# ST_LINK_V2.net
KiCad netlist of a schematic drawn in Altium Designer
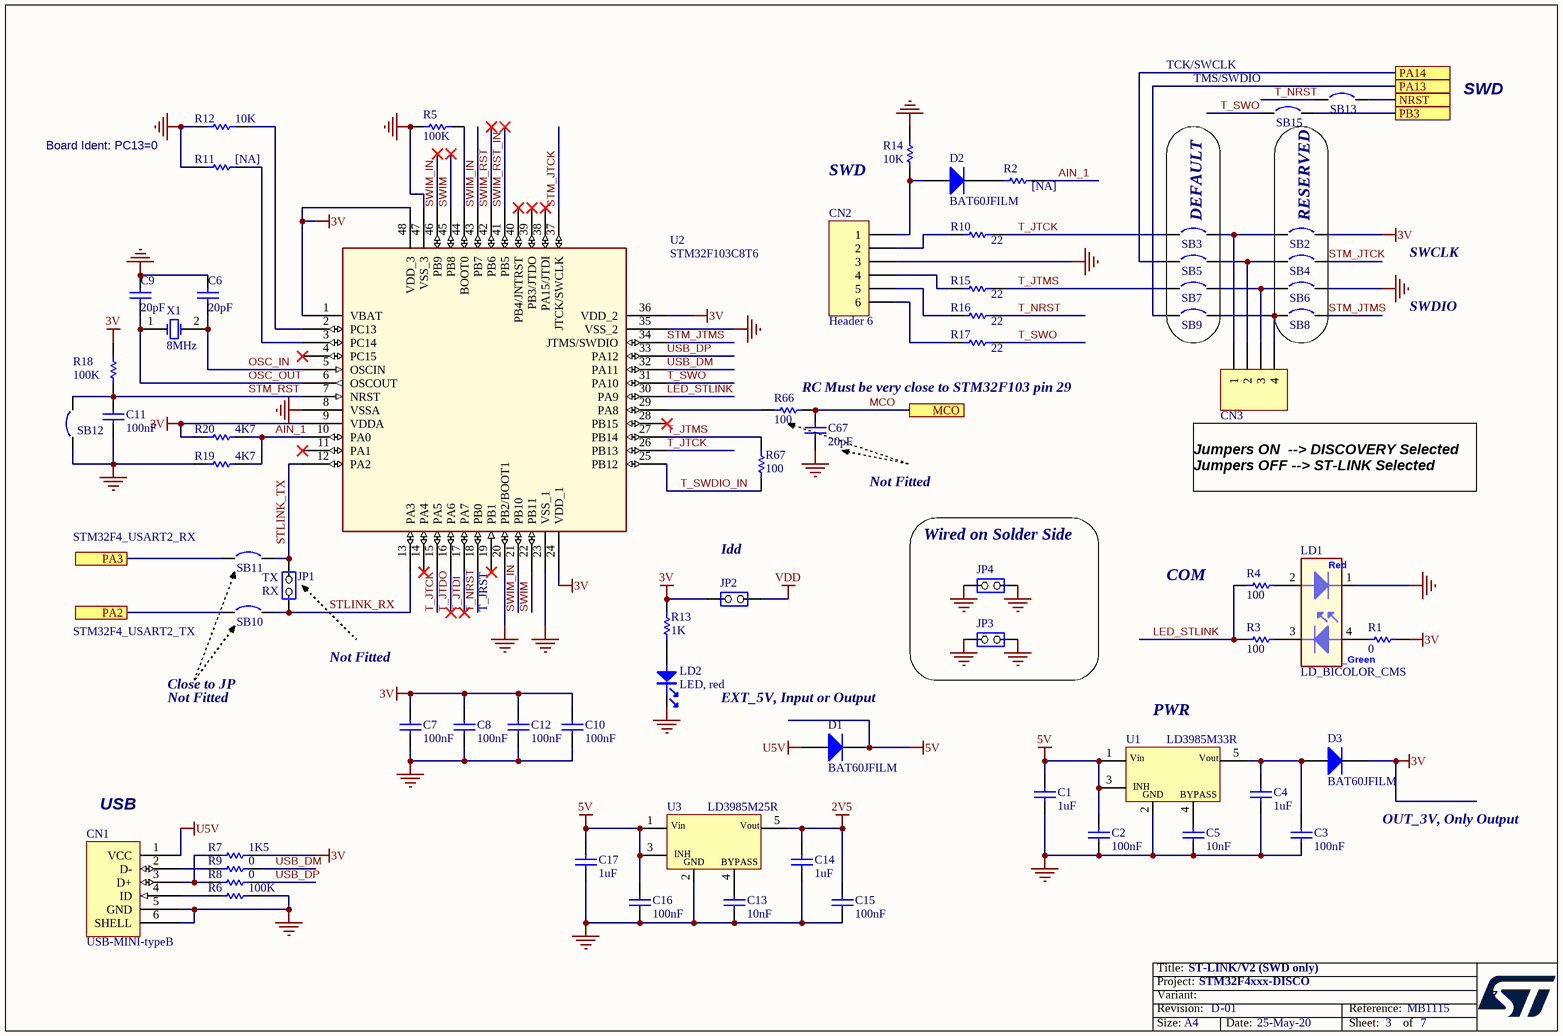
[diagram p0: ST_LINK_V2.SCHDOC]

(export (version "E")
  (design (tool "Eeschema 10.0.6"))
  (components
    (comp (ref "C1")
      (value "1uF")
      (footprint "0603C (Primary)")
      (description "Capacitor,1uF,16V,X5R,10%,0603,YAGEO")
      (libsource (lib "MCD_TOOLS") (part "Cap_1uF_X5R_10%_0603"))
    )
    (comp (ref "C2")
      (value "100nF")
      (footprint "0402C (Primary)")
      (description "Capacitor,100nF,16V,X7R,10%,0402,YAGEO")
      (libsource (lib "MCD_TOOLS") (part "Cap_100nF_X7R_10%_0402"))
    )
    (comp (ref "C3")
      (value "100nF")
      (footprint "0402C (Primary)")
      (description "Capacitor,100nF,16V,X7R,10%,0402,YAGEO")
      (libsource (lib "MCD_TOOLS") (part "Cap_100nF_X7R_10%_0402"))
    )
    (comp (ref "C4")
      (value "1uF")
      (footprint "0603C (Primary)")
      (description "Capacitor,1uF,16V,X5R,10%,0603,YAGEO")
      (libsource (lib "MCD_TOOLS") (part "Cap_1uF_X5R_10%_0603"))
    )
    (comp (ref "C5")
      (value "10nF")
      (footprint "0603C (Primary)")
      (description "Capacitor,10nF,50V,X7R,10%,0603,YAGEO")
      (libsource (lib "MCD_TOOLS") (part "Cap_10nF_X7R_10%_0603"))
    )
    (comp (ref "C6")
      (value "20pF")
      (footprint "0402C (Primary)")
      (description "Capacitor,20pF,50V,NPO,5%,0402,YAGEO")
      (libsource (lib "MCD_TOOLS") (part "Cap_20pF_NPO_5%_0402"))
    )
    (comp (ref "C7")
      (value "100nF")
      (footprint "0402C (Primary)")
      (description "Capacitor,100nF,16V,X7R,10%,0402,YAGEO")
      (libsource (lib "MCD_TOOLS") (part "Cap_100nF_X7R_10%_0402"))
    )
    (comp (ref "C8")
      (value "100nF")
      (footprint "0402C (Primary)")
      (description "Capacitor,100nF,16V,X7R,10%,0402,YAGEO")
      (libsource (lib "MCD_TOOLS") (part "Cap_100nF_X7R_10%_0402"))
    )
    (comp (ref "C9")
      (value "20pF")
      (footprint "0402C (Primary)")
      (description "Capacitor,20pF,50V,NPO,5%,0402,YAGEO")
      (libsource (lib "MCD_TOOLS") (part "Cap_20pF_NPO_5%_0402"))
    )
    (comp (ref "C10")
      (value "100nF")
      (footprint "0402C (Primary)")
      (description "Capacitor,100nF,16V,X7R,10%,0402,YAGEO")
      (libsource (lib "MCD_TOOLS") (part "Cap_100nF_X7R_10%_0402"))
    )
    (comp (ref "C11")
      (value "100nF")
      (footprint "0402C (Primary)")
      (description "Capacitor,100nF,16V,X7R,10%,0402,YAGEO")
      (libsource (lib "MCD_TOOLS") (part "Cap_100nF_X7R_10%_0402"))
    )
    (comp (ref "C12")
      (value "100nF")
      (footprint "0402C (Primary)")
      (description "Capacitor,100nF,16V,X7R,10%,0402,YAGEO")
      (libsource (lib "MCD_TOOLS") (part "Cap_100nF_X7R_10%_0402"))
    )
    (comp (ref "C13")
      (value "10nF")
      (footprint "0603C (Primary)")
      (description "Capacitor,10nF,50V,X7R,10%,0603,YAGEO")
      (libsource (lib "MCD_TOOLS") (part "Cap_10nF_X7R_10%_0603"))
    )
    (comp (ref "C14")
      (value "1uF")
      (footprint "0603C (Primary)")
      (description "Capacitor,1uF,16V,X5R,10%,0603,YAGEO")
      (libsource (lib "MCD_TOOLS") (part "Cap_1uF_X5R_10%_0603"))
    )
    (comp (ref "C15")
      (value "100nF")
      (footprint "0402C (Primary)")
      (description "Capacitor,100nF,16V,X7R,10%,0402,YAGEO")
      (libsource (lib "MCD_TOOLS") (part "Cap_100nF_X7R_10%_0402"))
    )
    (comp (ref "C16")
      (value "100nF")
      (footprint "0402C (Primary)")
      (description "Capacitor,100nF,16V,X7R,10%,0402,YAGEO")
      (libsource (lib "MCD_TOOLS") (part "Cap_100nF_X7R_10%_0402"))
    )
    (comp (ref "C17")
      (value "1uF")
      (footprint "0603C (Primary)")
      (description "Capacitor,1uF,16V,X5R,10%,0603,YAGEO")
      (libsource (lib "MCD_TOOLS") (part "Cap_1uF_X5R_10%_0603"))
    )
    (comp (ref "C67")
      (value "20pF")
      (footprint "0402C (Primary)")
      (description "Capacitor,20pF,50V,NPO,5%,0402,YAGEO")
      (libsource (lib "MCD_TOOLS") (part "Cap_20pF_NPO_5%_0402"))
    )
    (comp (ref "CN1")
      (value "USB-MINI-typeB")
      (footprint "USB-MINI-B-SMD (Primary)")
      (description "USB-MINI-typeB connector")
      (libsource (lib "MCD_TOOLS") (part "USB-MINI-typeB connector"))
    )
    (comp (ref "CN2")
      (value "Header 6")
      (footprint "HDR1X6 (Primary)")
      (description "Header, 6-Pin")
      (fields (field (name "PUBLISHER") "Altium Limited"))
      (libsource (lib "Miscellaneous Connectors") (part "Header 6"))
    )
    (comp (ref "CN3")
      (value "Header 4")
      (footprint "Header 4 (Primary)")
      (description "Header, 4-Pin")
      (fields (field (name "PUBLISHER") "Altium Limited"))
      (libsource (lib "MB963_1") (part "Header 4"))
    )
    (comp (ref "D1")
      (value "BAT60JFILM")
      (footprint "SOD323/A (Primary)")
      (libsource (lib "MCD_TOOLS") (part "BAT60JFILM"))
    )
    (comp (ref "D2")
      (value "BAT60JFILM")
      (footprint "SOD323/A (Primary)")
      (libsource (lib "MCD_TOOLS") (part "BAT60JFILM"))
    )
    (comp (ref "D3")
      (value "BAT60JFILM")
      (footprint "SOD323/A (Primary)")
      (libsource (lib "MCD_TOOLS") (part "BAT60JFILM"))
    )
    (comp (ref "JP1")
      (value "JP2")
      (footprint "SIP2/2.54 (Primary)")
      (libsource (lib "MCD_TOOLS") (part "JP2"))
    )
    (comp (ref "JP2") (value "~") (footprint "SIP2/2.54 (Primary)") (libsource (lib "*") (part "JP2")))
    (comp (ref "JP3") (value "~") (footprint "SIP2/2.54 (Primary)") (libsource (lib "*") (part "JP2")))
    (comp (ref "JP4") (value "~") (footprint "SIP2/2.54 (Primary)") (libsource (lib "*") (part "JP2")))
    (comp (ref "LD1")
      (value "LD_BICOLOR_CMS")
      (footprint "HSMF-A201 (Primary)")
      (description "Bicolor Led")
      (libsource (lib "MCD_TOOLS") (part "LD_BICOLOR_CMS"))
    )
    (comp (ref "LD2")
      (value "LED, red")
      (footprint "0603D (Primary)")
      (description "LED, red, 0603")
      (libsource (lib "MCD_TOOLS") (part "LED_red"))
    )
    (comp (ref "R1")
      (value "0")
      (footprint "0402R (Primary)")
      (description "Resistor,0,0402")
      (libsource (lib "MCD_TOOLS") (part "Res_0_0402"))
    )
    (comp (ref "R2")
      (value "[NA]")
      (footprint "0402R (Primary)")
      (description "Resistor,[NA],0402")
      (libsource (lib "MCD_TOOLS") (part "Res_NA_0402"))
    )
    (comp (ref "R3")
      (value "100")
      (footprint "0402R (Primary)")
      (description "Resistor")
      (fields (field (name "PUBLISHER") "Altium Limited"))
      (libsource (lib "MB915_1") (part "res1"))
    )
    (comp (ref "R4")
      (value "100")
      (footprint "0402R (Primary)")
      (description "Resistor")
      (fields (field (name "PUBLISHER") "Altium Limited"))
      (libsource (lib "MB915_1") (part "res1"))
    )
    (comp (ref "R5")
      (value "100K")
      (footprint "0402R (Primary)")
      (description "Resistor")
      (fields (field (name "PUBLISHER") "Altium Limited"))
      (libsource (lib "MB915_1") (part "res1"))
    )
    (comp (ref "R6")
      (value "100K")
      (footprint "0402R (Primary)")
      (description "Resistor")
      (fields (field (name "PUBLISHER") "Altium Limited"))
      (libsource (lib "MB915_1") (part "res1"))
    )
    (comp (ref "R7")
      (value "1K5")
      (footprint "0402R (Primary)")
      (description "Resistor")
      (fields (field (name "PUBLISHER") "Altium Limited"))
      (libsource (lib "MB915_1") (part "res1"))
    )
    (comp (ref "R8")
      (value "0")
      (footprint "0402R (Primary)")
      (description "Resistor,0,0402")
      (libsource (lib "MCD_TOOLS") (part "Res_0_0402"))
    )
    (comp (ref "R9")
      (value "0")
      (footprint "0402R (Primary)")
      (description "Resistor,0,0402")
      (libsource (lib "MCD_TOOLS") (part "Res_0_0402"))
    )
    (comp (ref "R10")
      (value "22")
      (footprint "0402R (Primary)")
      (description "Resistor")
      (fields (field (name "PUBLISHER") "Altium Limited"))
      (libsource (lib "MB915_1") (part "res1"))
    )
    (comp (ref "R11")
      (value "[NA]")
      (footprint "0402R (Primary)")
      (description "Resistor,[NA],0402")
      (libsource (lib "MCD_TOOLS") (part "Res_NA_0402"))
    )
    (comp (ref "R12")
      (value "10K")
      (footprint "0402R (Primary)")
      (description "Resistor")
      (fields (field (name "PUBLISHER") "Altium Limited"))
      (libsource (lib "MB915_1") (part "res1"))
    )
    (comp (ref "R13")
      (value "1K")
      (footprint "0402R (Primary)")
      (description "Resistor")
      (fields (field (name "PUBLISHER") "Altium Limited"))
      (libsource (lib "MB915_1") (part "res1"))
    )
    (comp (ref "R14")
      (value "10K")
      (footprint "0402R (Primary)")
      (description "Resistor")
      (fields (field (name "PUBLISHER") "Altium Limited"))
      (libsource (lib "MB915_1") (part "res1"))
    )
    (comp (ref "R15")
      (value "22")
      (footprint "0402R (Primary)")
      (description "Resistor")
      (fields (field (name "PUBLISHER") "Altium Limited"))
      (libsource (lib "MB915_1") (part "res1"))
    )
    (comp (ref "R16")
      (value "22")
      (footprint "0402R (Primary)")
      (description "Resistor")
      (fields (field (name "PUBLISHER") "Altium Limited"))
      (libsource (lib "MB915_1") (part "res1"))
    )
    (comp (ref "R17")
      (value "22")
      (footprint "0402R (Primary)")
      (description "Resistor")
      (fields (field (name "PUBLISHER") "Altium Limited"))
      (libsource (lib "MB915_1") (part "res1"))
    )
    (comp (ref "R18")
      (value "100K")
      (footprint "0402R (Primary)")
      (description "Resistor")
      (fields (field (name "PUBLISHER") "Altium Limited"))
      (libsource (lib "MB915_1") (part "res1"))
    )
    (comp (ref "R19")
      (value "4K7")
      (footprint "0402R (Primary)")
      (description "Resistor")
      (fields (field (name "PUBLISHER") "Altium Limited"))
      (libsource (lib "MB915_1") (part "res1"))
    )
    (comp (ref "R20")
      (value "4K7")
      (footprint "0402R (Primary)")
      (description "Resistor")
      (fields (field (name "PUBLISHER") "Altium Limited"))
      (libsource (lib "MB915_1") (part "res1"))
    )
    (comp (ref "R66")
      (value "100")
      (footprint "0402R (Primary)")
      (description "Resistor")
      (fields (field (name "PUBLISHER") "Altium Limited"))
      (libsource (lib "MB915_1") (part "res1"))
    )
    (comp (ref "R67")
      (value "100")
      (footprint "0402R (Primary)")
      (description "Resistor")
      (fields (field (name "PUBLISHER") "Altium Limited"))
      (libsource (lib "MB915_1") (part "res1"))
    )
    (comp (ref "SB2")
      (value "Circuit Breaker")
      (footprint "JP2_SMD (Primary)")
      (libsource (lib "MCD_TOOLS") (part "Circuit Breaker"))
    )
    (comp (ref "SB3")
      (value "Circuit Breaker")
      (footprint "JP2_SMD (Primary)")
      (libsource (lib "MCD_TOOLS") (part "Circuit Breaker"))
    )
    (comp (ref "SB4")
      (value "Circuit Breaker")
      (footprint "JP2_SMD (Primary)")
      (libsource (lib "MCD_TOOLS") (part "Circuit Breaker"))
    )
    (comp (ref "SB5")
      (value "Circuit Breaker")
      (footprint "JP2_SMD (Primary)")
      (libsource (lib "MCD_TOOLS") (part "Circuit Breaker"))
    )
    (comp (ref "SB6")
      (value "Circuit Breaker")
      (footprint "JP2_SMD (Primary)")
      (libsource (lib "MCD_TOOLS") (part "Circuit Breaker"))
    )
    (comp (ref "SB7")
      (value "Circuit Breaker")
      (footprint "JP2_SMD (Primary)")
      (libsource (lib "MCD_TOOLS") (part "Circuit Breaker"))
    )
    (comp (ref "SB8")
      (value "Circuit Breaker")
      (footprint "JP2_SMD (Primary)")
      (libsource (lib "MCD_TOOLS") (part "Circuit Breaker"))
    )
    (comp (ref "SB9")
      (value "Circuit Breaker")
      (footprint "JP2_SMD (Primary)")
      (libsource (lib "MCD_TOOLS") (part "Circuit Breaker"))
    )
    (comp (ref "SB10")
      (value "Circuit Breaker")
      (footprint "JP2_SMD (Primary)")
      (libsource (lib "MCD_TOOLS") (part "Circuit Breaker"))
    )
    (comp (ref "SB11")
      (value "Circuit Breaker")
      (footprint "JP2_SMD (Primary)")
      (libsource (lib "MCD_TOOLS") (part "Circuit Breaker"))
    )
    (comp (ref "SB12")
      (value "Circuit Breaker")
      (footprint "JP2_SMD (Primary)")
      (libsource (lib "MCD_TOOLS") (part "Circuit Breaker"))
    )
    (comp (ref "SB13")
      (value "Circuit Breaker")
      (footprint "JP2_SMD (Primary)")
      (libsource (lib "MCD_TOOLS") (part "Circuit Breaker"))
    )
    (comp (ref "SB15")
      (value "Circuit Breaker")
      (footprint "JP2_SMD (Primary)")
      (libsource (lib "MCD_TOOLS") (part "Circuit Breaker"))
    )
    (comp (ref "U1")
      (value "LD3985M33R")
      (footprint "SOT-23-5L (Primary)")
      (description "Ultra low drop-low noise BiCMOS voltage, regulators low ESR capacitors compatible")
      (libsource (lib "MCD_TOOLS") (part "LD3985M33R"))
    )
    (comp (ref "U2")
      (value "STM32F103C8T6")
      (footprint "LQFP48 (Primary)")
      (description "Medium-density performance line ARM-based 32-bit MCU with 64KB Flash")
      (libsource (lib "MCD_TOOLS") (part "STM32F103C8T6"))
    )
    (comp (ref "U3")
      (value "LD3985M25R")
      (footprint "SOT-23-5L (Primary)")
      (description "Ultra low drop-low noise BiCMOS voltage, regulators low ESR capacitors compatible")
      (libsource (lib "MCD_TOOLS") (part "LD3985M25R"))
    )
    (comp (ref "X1")
      (value "8MHz")
      (footprint "XTAL1 (Primary)")
      (description "Crystal Oscillator,8Mhz,20PF,20PPM,-10-70 degree,DIP,HC-49S")
      (libsource (lib "MCD_TOOLS") (part "XTAL_8MHZ_20PPM"))
    )
  )
  (nets
    (net (code "1") (name "/AIN_1") (class "Default")
      (node (ref "R19") (pin "2") (pinfunction "2_2") (pintype "passive"))
      (node (ref "R2") (pin "2") (pinfunction "2_2") (pintype "passive"))
      (node (ref "R20") (pin "2") (pinfunction "2_2") (pintype "passive"))
      (node (ref "U2") (pin "10") (pinfunction "PA0_10") (pintype "bidirectional"))
    )
    (net (code "2") (name "/LED_STLINK") (class "Default")
      (node (ref "R3") (pin "1") (pinfunction "1_1") (pintype "passive"))
      (node (ref "R4") (pin "1") (pinfunction "1_1") (pintype "passive"))
      (node (ref "U2") (pin "30") (pinfunction "PA9_30") (pintype "bidirectional"))
    )
    (net (code "3") (name "/MCO") (class "Default")
      (node (ref "C67") (pin "1") (pinfunction "1_1") (pintype "passive"))
      (node (ref "R66") (pin "2") (pinfunction "2_2") (pintype "passive"))
    )
    (net (code "4") (name "/NRST") (class "Default")
      (node (ref "SB13") (pin "2") (pinfunction "2_2") (pintype "passive"))
    )
    (net (code "5") (name "/OSC_IN") (class "Default")
      (node (ref "C6") (pin "2") (pinfunction "2_2") (pintype "passive"))
      (node (ref "U2") (pin "5") (pinfunction "OSCIN_5") (pintype "input"))
      (node (ref "X1") (pin "2") (pinfunction "OSC2_2") (pintype "passive"))
    )
    (net (code "6") (name "/OSC_OUT") (class "Default")
      (node (ref "C9") (pin "2") (pinfunction "2_2") (pintype "passive"))
      (node (ref "U2") (pin "6") (pinfunction "OSCOUT_6") (pintype "output"))
      (node (ref "X1") (pin "1") (pinfunction "OSC1_1") (pintype "passive"))
    )
    (net (code "7") (name "/PA2") (class "Default")
      (node (ref "SB10") (pin "1") (pinfunction "1_1") (pintype "passive"))
    )
    (net (code "8") (name "/PA3") (class "Default")
      (node (ref "SB11") (pin "1") (pinfunction "1_1") (pintype "passive"))
    )
    (net (code "9") (name "/PA13") (class "Default")
      (node (ref "SB9") (pin "1") (pinfunction "1_1") (pintype "passive"))
    )
    (net (code "10") (name "/PA14") (class "Default")
      (node (ref "SB5") (pin "1") (pinfunction "1_1") (pintype "passive"))
    )
    (net (code "11") (name "/PB3") (class "Default")
      (node (ref "SB15") (pin "2") (pinfunction "2_2") (pintype "passive"))
    )
    (net (code "12") (name "/STLINK_RX") (class "Default")
      (node (ref "JP1") (pin "1") (pinfunction "COMMON_1") (pintype "passive"))
      (node (ref "SB10") (pin "2") (pinfunction "2_2") (pintype "passive"))
      (node (ref "U2") (pin "13") (pinfunction "PA3_13") (pintype "bidirectional"))
    )
    (net (code "13") (name "/STLINK_TX") (class "Default")
      (node (ref "JP1") (pin "2") (pinfunction "NO_2") (pintype "passive"))
      (node (ref "SB11") (pin "2") (pinfunction "2_2") (pintype "passive"))
      (node (ref "U2") (pin "12") (pinfunction "PA2_12") (pintype "bidirectional"))
    )
    (net (code "14") (name "/STM_JTCK") (class "Default")
      (node (ref "SB4") (pin "2") (pinfunction "2_2") (pintype "passive"))
      (node (ref "U2") (pin "37") (pinfunction "JTCK/SWCLK_37") (pintype "bidirectional"))
    )
    (net (code "15") (name "/STM_JTMS") (class "Default")
      (node (ref "SB8") (pin "2") (pinfunction "2_2") (pintype "passive"))
      (node (ref "U2") (pin "34") (pinfunction "JTMS/SWDIO_34") (pintype "bidirectional"))
    )
    (net (code "16") (name "/STM_RST") (class "Default")
      (node (ref "C11") (pin "2") (pinfunction "2_2") (pintype "passive"))
      (node (ref "R18") (pin "1") (pinfunction "1_1") (pintype "passive"))
      (node (ref "SB12") (pin "2") (pinfunction "2_2") (pintype "passive"))
      (node (ref "U2") (pin "7") (pinfunction "NRST_7") (pintype "input"))
    )
    (net (code "17") (name "/SWIM") (class "Default")
      (node (ref "U2") (pin "22") (pinfunction "PB11_22") (pintype "bidirectional"))
      (node (ref "U2") (pin "45") (pinfunction "PB8_45") (pintype "bidirectional"))
    )
    (net (code "18") (name "/SWIM_IN") (class "Default")
      (node (ref "U2") (pin "21") (pinfunction "PB10_21") (pintype "bidirectional"))
      (node (ref "U2") (pin "43") (pinfunction "PB7_43") (pintype "bidirectional"))
      (node (ref "U2") (pin "46") (pinfunction "PB9_46") (pintype "bidirectional"))
    )
    (net (code "19") (name "/SWIM_RST") (class "Default")
      (node (ref "U2") (pin "42") (pinfunction "PB6_42") (pintype "bidirectional+no_connect"))
    )
    (net (code "20") (name "/SWIM_RST_IN") (class "Default")
      (node (ref "U2") (pin "41") (pinfunction "PB5_41") (pintype "bidirectional+no_connect"))
    )
    (net (code "21") (name "/T_JTCK") (class "Default")
      (node (ref "R10") (pin "2") (pinfunction "2_2") (pintype "passive"))
      (node (ref "SB3") (pin "1") (pinfunction "1_1") (pintype "passive"))
      (node (ref "U2") (pin "15") (pinfunction "PA5_15") (pintype "bidirectional"))
      (node (ref "U2") (pin "26") (pinfunction "PB13_26") (pintype "bidirectional"))
    )
    (net (code "22") (name "/T_JTDI") (class "Default")
      (node (ref "U2") (pin "17") (pinfunction "PA7_17") (pintype "bidirectional+no_connect"))
    )
    (net (code "23") (name "/T_JTDO") (class "Default")
      (node (ref "U2") (pin "16") (pinfunction "PA6_16") (pintype "bidirectional+no_connect"))
    )
    (net (code "24") (name "/T_JTMS") (class "Default")
      (node (ref "R15") (pin "2") (pinfunction "2_2") (pintype "passive"))
      (node (ref "R67") (pin "2") (pinfunction "2_2") (pintype "passive"))
      (node (ref "SB7") (pin "1") (pinfunction "1_1") (pintype "passive"))
      (node (ref "U2") (pin "27") (pinfunction "PB14_27") (pintype "bidirectional"))
    )
    (net (code "25") (name "/T_NRST") (class "Default")
      (node (ref "R16") (pin "2") (pinfunction "2_2") (pintype "passive"))
      (node (ref "SB13") (pin "1") (pinfunction "1_1") (pintype "passive"))
      (node (ref "U2") (pin "18") (pinfunction "PB0_18") (pintype "bidirectional"))
    )
    (net (code "26") (name "/T_SWDIO_IN") (class "Default")
      (node (ref "R67") (pin "1") (pinfunction "1_1") (pintype "passive"))
      (node (ref "U2") (pin "25") (pinfunction "PB12_25") (pintype "bidirectional"))
    )
    (net (code "27") (name "/T_SWO") (class "Default")
      (node (ref "R17") (pin "2") (pinfunction "2_2") (pintype "passive"))
      (node (ref "SB15") (pin "1") (pinfunction "1_1") (pintype "passive"))
      (node (ref "U2") (pin "31") (pinfunction "PA10_31") (pintype "bidirectional"))
    )
    (net (code "28") (name "/USB_DM") (class "Default")
      (node (ref "R9") (pin "2") (pinfunction "2_2") (pintype "passive"))
      (node (ref "U2") (pin "32") (pinfunction "PA11_32") (pintype "bidirectional"))
    )
    (net (code "29") (name "/USB_DP") (class "Default")
      (node (ref "R8") (pin "2") (pinfunction "2_2") (pintype "passive"))
      (node (ref "U2") (pin "33") (pinfunction "PA12_33") (pintype "bidirectional"))
    )
    (net (code "30") (name "2V5") (class "Default")
      (node (ref "C14") (pin "1") (pinfunction "1_1") (pintype "passive"))
      (node (ref "C15") (pin "2") (pinfunction "2_2") (pintype "passive"))
      (node (ref "U3") (pin "5") (pinfunction "Vout_5") (pintype "passive"))
    )
    (net (code "31") (name "3V") (class "Default")
      (node (ref "C10") (pin "2") (pinfunction "2_2") (pintype "passive"))
      (node (ref "C12") (pin "1") (pinfunction "1_1") (pintype "passive"))
      (node (ref "C7") (pin "2") (pinfunction "2_2") (pintype "passive"))
      (node (ref "C8") (pin "2") (pinfunction "2_2") (pintype "passive"))
      (node (ref "D3") (pin "2") (pinfunction "K_2") (pintype "passive"))
      (node (ref "JP2") (pin "1") (pinfunction "COMMON_1") (pintype "passive"))
      (node (ref "R1") (pin "2") (pinfunction "2_2") (pintype "passive"))
      (node (ref "R13") (pin "2") (pinfunction "2_2") (pintype "passive"))
      (node (ref "R18") (pin "2") (pinfunction "2_2") (pintype "passive"))
      (node (ref "R20") (pin "1") (pinfunction "1_1") (pintype "passive"))
      (node (ref "R7") (pin "2") (pinfunction "2_2") (pintype "passive"))
      (node (ref "SB2") (pin "2") (pinfunction "2_2") (pintype "passive"))
      (node (ref "U2") (pin "1") (pinfunction "VBAT_1") (pintype "power_in"))
      (node (ref "U2") (pin "24") (pinfunction "VDD_1_24") (pintype "power_in"))
      (node (ref "U2") (pin "36") (pinfunction "VDD_2_36") (pintype "power_in"))
      (node (ref "U2") (pin "48") (pinfunction "VDD_3_48") (pintype "power_in"))
      (node (ref "U2") (pin "9") (pinfunction "VDDA_9") (pintype "power_in"))
    )
    (net (code "32") (name "5V") (class "Default")
      (node (ref "C1") (pin "2") (pinfunction "2_2") (pintype "passive"))
      (node (ref "C16") (pin "2") (pinfunction "2_2") (pintype "passive"))
      (node (ref "C17") (pin "2") (pinfunction "2_2") (pintype "passive"))
      (node (ref "C2") (pin "2") (pinfunction "2_2") (pintype "passive"))
      (node (ref "D1") (pin "2") (pinfunction "K_2") (pintype "passive"))
      (node (ref "U1") (pin "1") (pinfunction "Vin_1") (pintype "passive"))
      (node (ref "U1") (pin "3") (pinfunction "CE_3") (pintype "passive"))
      (node (ref "U3") (pin "1") (pinfunction "Vin_1") (pintype "passive"))
      (node (ref "U3") (pin "3") (pinfunction "CE_3") (pintype "passive"))
    )
    (net (code "33") (name "GND") (class "Default")
      (node (ref "C1") (pin "1") (pinfunction "1_1") (pintype "passive"))
      (node (ref "C10") (pin "1") (pinfunction "1_1") (pintype "passive"))
      (node (ref "C11") (pin "1") (pinfunction "1_1") (pintype "passive"))
      (node (ref "C12") (pin "2") (pinfunction "2_2") (pintype "passive"))
      (node (ref "C13") (pin "1") (pinfunction "1_1") (pintype "passive"))
      (node (ref "C14") (pin "2") (pinfunction "2_2") (pintype "passive"))
      (node (ref "C15") (pin "1") (pinfunction "1_1") (pintype "passive"))
      (node (ref "C16") (pin "1") (pinfunction "1_1") (pintype "passive"))
      (node (ref "C17") (pin "1") (pinfunction "1_1") (pintype "passive"))
      (node (ref "C2") (pin "1") (pinfunction "1_1") (pintype "passive"))
      (node (ref "C3") (pin "1") (pinfunction "1_1") (pintype "passive"))
      (node (ref "C4") (pin "2") (pinfunction "2_2") (pintype "passive"))
      (node (ref "C5") (pin "1") (pinfunction "1_1") (pintype "passive"))
      (node (ref "C6") (pin "1") (pinfunction "1_1") (pintype "passive"))
      (node (ref "C67") (pin "2") (pinfunction "2_2") (pintype "passive"))
      (node (ref "C7") (pin "1") (pinfunction "1_1") (pintype "passive"))
      (node (ref "C8") (pin "1") (pinfunction "1_1") (pintype "passive"))
      (node (ref "C9") (pin "1") (pinfunction "1_1") (pintype "passive"))
      (node (ref "CN1") (pin "5") (pinfunction "GND_5") (pintype "passive"))
      (node (ref "CN1") (pin "6") (pinfunction "SHELL_6") (pintype "passive"))
      (node (ref "CN2") (pin "3") (pinfunction "3_3") (pintype "passive"))
      (node (ref "JP3") (pin "1") (pinfunction "COMMON_1") (pintype "passive"))
      (node (ref "JP3") (pin "2") (pinfunction "NO_2") (pintype "passive"))
      (node (ref "JP4") (pin "1") (pinfunction "COMMON_1") (pintype "passive"))
      (node (ref "JP4") (pin "2") (pinfunction "NO_2") (pintype "passive"))
      (node (ref "LD1") (pin "1") (pinfunction "1_1") (pintype "passive"))
      (node (ref "LD2") (pin "2") (pintype "passive"))
      (node (ref "R11") (pin "1") (pinfunction "1_1") (pintype "passive"))
      (node (ref "R12") (pin "1") (pinfunction "1_1") (pintype "passive"))
      (node (ref "R14") (pin "2") (pinfunction "2_2") (pintype "passive"))
      (node (ref "R19") (pin "1") (pinfunction "1_1") (pintype "passive"))
      (node (ref "R5") (pin "1") (pinfunction "1_1") (pintype "passive"))
      (node (ref "R6") (pin "2") (pinfunction "2_2") (pintype "passive"))
      (node (ref "SB12") (pin "1") (pinfunction "1_1") (pintype "passive"))
      (node (ref "SB6") (pin "2") (pinfunction "2_2") (pintype "passive"))
      (node (ref "U1") (pin "2") (pinfunction "GND_2") (pintype "passive"))
      (node (ref "U2") (pin "20") (pinfunction "PB2/BOOT1_20") (pintype "bidirectional"))
      (node (ref "U2") (pin "23") (pinfunction "VSS_1_23") (pintype "power_in"))
      (node (ref "U2") (pin "35") (pinfunction "VSS_2_35") (pintype "power_in"))
      (node (ref "U2") (pin "47") (pinfunction "VSS_3_47") (pintype "power_in"))
      (node (ref "U2") (pin "8") (pinfunction "VSSA_8") (pintype "power_in"))
      (node (ref "U3") (pin "2") (pinfunction "GND_2") (pintype "passive"))
    )
    (net (code "34") (name "Net-(CN1-D+)") (class "Default")
      (node (ref "CN1") (pin "3") (pinfunction "D+_3") (pintype "bidirectional"))
      (node (ref "R7") (pin "1") (pinfunction "1_1") (pintype "passive"))
      (node (ref "R8") (pin "1") (pinfunction "1_1") (pintype "passive"))
    )
    (net (code "35") (name "Net-(CN1-D-)") (class "Default")
      (node (ref "CN1") (pin "2") (pinfunction "D-_2") (pintype "bidirectional"))
      (node (ref "R9") (pin "1") (pinfunction "1_1") (pintype "passive"))
    )
    (net (code "36") (name "Net-(CN1-ID)") (class "Default")
      (node (ref "CN1") (pin "4") (pinfunction "ID_4") (pintype "input"))
      (node (ref "R6") (pin "1") (pinfunction "1_1") (pintype "passive"))
    )
    (net (code "37") (name "Net-(CN2-Pad2)") (class "Default")
      (node (ref "CN2") (pin "2") (pinfunction "2_2") (pintype "passive"))
      (node (ref "R10") (pin "1") (pinfunction "1_1") (pintype "passive"))
    )
    (net (code "38") (name "Net-(CN2-Pad4)") (class "Default")
      (node (ref "CN2") (pin "4") (pinfunction "4_4") (pintype "passive"))
      (node (ref "R15") (pin "1") (pinfunction "1_1") (pintype "passive"))
    )
    (net (code "39") (name "Net-(CN2-Pad5)") (class "Default")
      (node (ref "CN2") (pin "5") (pinfunction "5_5") (pintype "passive"))
      (node (ref "R16") (pin "1") (pinfunction "1_1") (pintype "passive"))
    )
    (net (code "40") (name "Net-(CN2-Pad6)") (class "Default")
      (node (ref "CN2") (pin "6") (pinfunction "6_6") (pintype "passive"))
      (node (ref "R17") (pin "1") (pinfunction "1_1") (pintype "passive"))
    )
    (net (code "41") (name "Net-(CN3-Pad1)") (class "Default")
      (node (ref "CN3") (pin "1") (pinfunction "1_1") (pintype "passive"))
      (node (ref "SB2") (pin "1") (pinfunction "1_1") (pintype "passive"))
      (node (ref "SB3") (pin "2") (pinfunction "2_2") (pintype "passive"))
    )
    (net (code "42") (name "Net-(CN3-Pad2)") (class "Default")
      (node (ref "CN3") (pin "2") (pinfunction "2_2") (pintype "passive"))
      (node (ref "SB4") (pin "1") (pinfunction "1_1") (pintype "passive"))
      (node (ref "SB5") (pin "2") (pinfunction "2_2") (pintype "passive"))
    )
    (net (code "43") (name "Net-(CN3-Pad3)") (class "Default")
      (node (ref "CN3") (pin "3") (pinfunction "3_3") (pintype "passive"))
      (node (ref "SB6") (pin "1") (pinfunction "1_1") (pintype "passive"))
      (node (ref "SB7") (pin "2") (pinfunction "2_2") (pintype "passive"))
    )
    (net (code "44") (name "Net-(CN3-Pad4)") (class "Default")
      (node (ref "CN3") (pin "4") (pinfunction "4_4") (pintype "passive"))
      (node (ref "SB8") (pin "1") (pinfunction "1_1") (pintype "passive"))
      (node (ref "SB9") (pin "2") (pinfunction "2_2") (pintype "passive"))
    )
    (net (code "45") (name "Net-(D2-A)") (class "Default")
      (node (ref "CN2") (pin "1") (pinfunction "1_1") (pintype "passive"))
      (node (ref "D2") (pin "1") (pinfunction "A_1") (pintype "passive"))
      (node (ref "R14") (pin "1") (pinfunction "1_1") (pintype "passive"))
    )
    (net (code "46") (name "Net-(D2-K)") (class "Default")
      (node (ref "D2") (pin "2") (pinfunction "K_2") (pintype "passive"))
      (node (ref "R2") (pin "1") (pinfunction "1_1") (pintype "passive"))
    )
    (net (code "47") (name "Net-(D3-A)") (class "Default")
      (node (ref "C3") (pin "2") (pinfunction "2_2") (pintype "passive"))
      (node (ref "C4") (pin "1") (pinfunction "1_1") (pintype "passive"))
      (node (ref "D3") (pin "1") (pinfunction "A_1") (pintype "passive"))
      (node (ref "U1") (pin "5") (pinfunction "Vout_5") (pintype "passive"))
    )
    (net (code "48") (name "Net-(LD1-Pad2)") (class "Default")
      (node (ref "LD1") (pin "2") (pinfunction "2_2") (pintype "passive"))
      (node (ref "R4") (pin "2") (pinfunction "2_2") (pintype "passive"))
    )
    (net (code "49") (name "Net-(LD1-Pad3)") (class "Default")
      (node (ref "LD1") (pin "3") (pinfunction "3_3") (pintype "passive"))
      (node (ref "R3") (pin "2") (pinfunction "2_2") (pintype "passive"))
    )
    (net (code "50") (name "Net-(LD1-Pad4)") (class "Default")
      (node (ref "LD1") (pin "4") (pinfunction "4_4") (pintype "passive"))
      (node (ref "R1") (pin "1") (pinfunction "1_1") (pintype "passive"))
    )
    (net (code "51") (name "Net-(LD2-Pad1)") (class "Default")
      (node (ref "LD2") (pin "1") (pintype "passive"))
      (node (ref "R13") (pin "1") (pinfunction "1_1") (pintype "passive"))
    )
    (net (code "52") (name "Net-(U1-BYPASS)") (class "Default")
      (node (ref "C5") (pin "2") (pinfunction "2_2") (pintype "passive"))
      (node (ref "U1") (pin "4") (pinfunction "BYPASS_4") (pintype "passive"))
    )
    (net (code "53") (name "Net-(U2-BOOT0)") (class "Default")
      (node (ref "R5") (pin "2") (pinfunction "2_2") (pintype "passive"))
      (node (ref "U2") (pin "44") (pinfunction "BOOT0_44") (pintype "bidirectional"))
    )
    (net (code "54") (name "Net-(U2-PA8)") (class "Default")
      (node (ref "R66") (pin "1") (pinfunction "1_1") (pintype "passive"))
      (node (ref "U2") (pin "29") (pinfunction "PA8_29") (pintype "bidirectional"))
    )
    (net (code "55") (name "Net-(U2-PC13)") (class "Default")
      (node (ref "R12") (pin "2") (pinfunction "2_2") (pintype "passive"))
      (node (ref "U2") (pin "2") (pinfunction "PC13_2") (pintype "bidirectional"))
    )
    (net (code "56") (name "Net-(U2-PC14)") (class "Default")
      (node (ref "R11") (pin "2") (pinfunction "2_2") (pintype "passive"))
      (node (ref "U2") (pin "3") (pinfunction "PC14_3") (pintype "bidirectional"))
    )
    (net (code "57") (name "Net-(U3-BYPASS)") (class "Default")
      (node (ref "C13") (pin "2") (pinfunction "2_2") (pintype "passive"))
      (node (ref "U3") (pin "4") (pinfunction "BYPASS_4") (pintype "passive"))
    )
    (net (code "58") (name "U5V") (class "Default")
      (node (ref "CN1") (pin "1") (pinfunction "VCC_1") (pintype "power_in"))
      (node (ref "D1") (pin "1") (pinfunction "A_1") (pintype "passive"))
    )
    (net (code "59") (name "VDD") (class "Default")
      (node (ref "JP2") (pin "2") (pinfunction "NO_2") (pintype "passive"))
    )
    (net (code "60") (name "unconnected-(U2-PA1-Pad11)") (class "Default")
      (node (ref "U2") (pin "11") (pinfunction "PA1_11") (pintype "bidirectional+no_connect"))
    )
    (net (code "61") (name "unconnected-(U2-PA4-Pad14)") (class "Default")
      (node (ref "U2") (pin "14") (pinfunction "PA4_14") (pintype "bidirectional+no_connect"))
    )
    (net (code "62") (name "unconnected-(U2-PA15{slash}JTDI-Pad38)") (class "Default")
      (node (ref "U2") (pin "38") (pinfunction "PA15/JTDI_38") (pintype "bidirectional+no_connect"))
    )
    (net (code "63") (name "unconnected-(U2-PB1-Pad19)") (class "Default")
      (node (ref "U2") (pin "19") (pinfunction "PB1_19") (pintype "input+no_connect"))
    )
    (net (code "64") (name "unconnected-(U2-PB3{slash}JTDO-Pad39)") (class "Default")
      (node (ref "U2") (pin "39") (pinfunction "PB3/JTDO_39") (pintype "bidirectional+no_connect"))
    )
    (net (code "65") (name "unconnected-(U2-PB4{slash}JNTRST-Pad40)") (class "Default")
      (node (ref "U2") (pin "40") (pinfunction "PB4/JNTRST_40") (pintype "bidirectional+no_connect"))
    )
    (net (code "66") (name "unconnected-(U2-PB15-Pad28)") (class "Default")
      (node (ref "U2") (pin "28") (pinfunction "PB15_28") (pintype "bidirectional+no_connect"))
    )
    (net (code "67") (name "unconnected-(U2-PC15-Pad4)") (class "Default")
      (node (ref "U2") (pin "4") (pinfunction "PC15_4") (pintype "bidirectional+no_connect"))
    )
  )
)
